# LCD_IO.net
KiCad netlist of a schematic drawn in Altium Designer
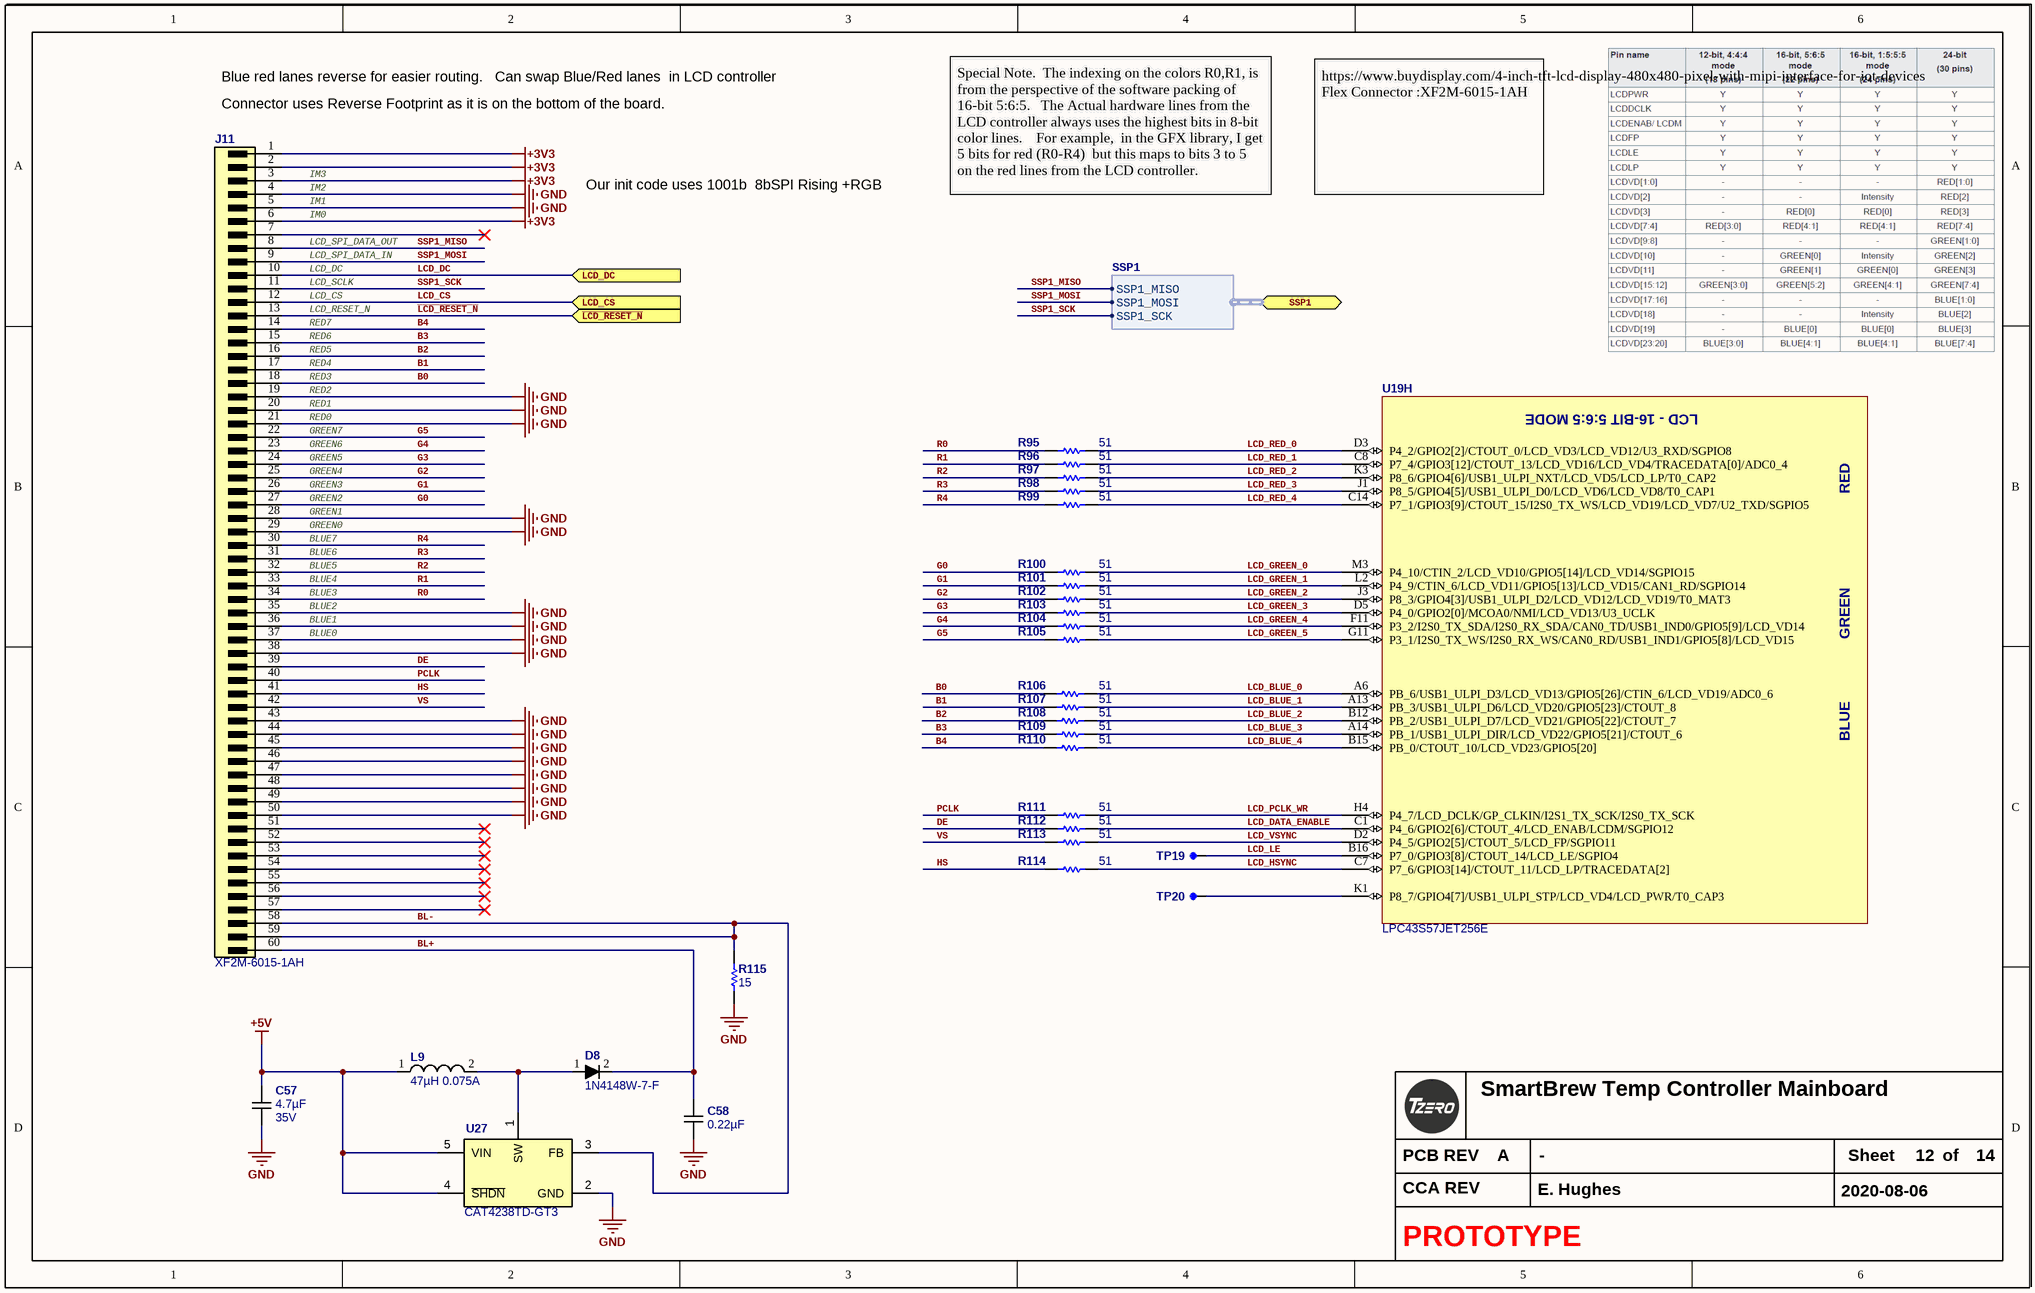
[diagram p0: LCD_IO.SchDoc]

(export (version "E")
  (design (tool "Eeschema 10.0.6"))
  (components
    (comp (ref "C57")
      (value "4.7µF")
      (footprint "C0805_1.50MM_HD")
      (description "CAP CER 4.7UF 35V X7R 0805")
      (fields
        (field (name "MANUFACTURER PART NUMBER") "CGA4J1X7R1V475K125AE")
        (field (name "MANUFACTURER") "TDK Corporation")
        (field (name "VOLTAGE - RATED") "35V")
      )
      (libsource (lib "Capacitors - TDK- AEC-Q200") (part "C_2P_NP"))
    )
    (comp (ref "C58")
      (value "0.22µF")
      (footprint "C0603_0.90MM_HD")
      (description "CAP CER 0.22UF 50V X7R 0603")
      (fields
        (field (name "MANUFACTURER PART NUMBER") "CGA3E3X7R1H224K080AB")
        (field (name "MANUFACTURER") "TDK Corporation")
      )
      (libsource (lib "Capacitors - TDK- AEC-Q200") (part "C_2P_NP"))
    )
    (comp (ref "D8")
      (value "1N4148W-7-F")
      (footprint "D_SOD-123_P")
      (description "DIODE SWITCH 100V 150MA SOD123")
      (fields (field (name "MANUFACTURER") "Diodes Inc"))
      (libsource (lib "Diodes") (part "DP_1A_2C"))
    )
    (comp (ref "J11")
      (value "XF2M-6015-1AH")
      (footprint "XF2M-6015-1AH - Reverse")
      (description "CONN FPC 60POS 0.50MM R/A")
      (fields (field (name "MANUFACTURER") "Omron"))
      (libsource (lib "eConnector_FPC") (part "XF2M-6015-1AH"))
    )
    (comp (ref "L9")
      (value "47µH 0.075A")
      (footprint "L0805_1.45MM_MD")
      (description "Inductor 47µH 0.075A")
      (fields (field (name "PART NUMBER") "LBR2012T470KV") (field (name "MANUFACTURER") "Taiyo Yuden"))
      (libsource (lib "Inductors") (part "L_2P"))
    )
    (comp (ref "R95")
      (value "51")
      (footprint "R0603_0.55MM_MD")
      (description "RES 51 OHM 1/10W 1% 0603 SMD")
      (fields
        (field (name "MANUFACTURER PART NUMBER") "ERJ-3EKF51R0V")
        (field (name "MANUFACTURER") "Panasonic Electronic Components")
      )
      (libsource (lib "Resistors - Panasonic - AEC-Q200") (part "R_2P"))
    )
    (comp (ref "R96")
      (value "51")
      (footprint "R0603_0.55MM_MD")
      (description "RES 51 OHM 1/10W 1% 0603 SMD")
      (fields
        (field (name "MANUFACTURER PART NUMBER") "ERJ-3EKF51R0V")
        (field (name "MANUFACTURER") "Panasonic Electronic Components")
      )
      (libsource (lib "Resistors - Panasonic - AEC-Q200") (part "R_2P"))
    )
    (comp (ref "R97")
      (value "51")
      (footprint "R0603_0.55MM_MD")
      (description "RES 51 OHM 1/10W 1% 0603 SMD")
      (fields
        (field (name "MANUFACTURER PART NUMBER") "ERJ-3EKF51R0V")
        (field (name "MANUFACTURER") "Panasonic Electronic Components")
      )
      (libsource (lib "Resistors - Panasonic - AEC-Q200") (part "R_2P"))
    )
    (comp (ref "R98")
      (value "51")
      (footprint "R0603_0.55MM_MD")
      (description "RES 51 OHM 1/10W 1% 0603 SMD")
      (fields
        (field (name "MANUFACTURER PART NUMBER") "ERJ-3EKF51R0V")
        (field (name "MANUFACTURER") "Panasonic Electronic Components")
      )
      (libsource (lib "Resistors - Panasonic - AEC-Q200") (part "R_2P"))
    )
    (comp (ref "R99")
      (value "51")
      (footprint "R0603_0.55MM_MD")
      (description "RES 51 OHM 1/10W 1% 0603 SMD")
      (fields
        (field (name "MANUFACTURER PART NUMBER") "ERJ-3EKF51R0V")
        (field (name "MANUFACTURER") "Panasonic Electronic Components")
      )
      (libsource (lib "Resistors - Panasonic - AEC-Q200") (part "R_2P"))
    )
    (comp (ref "R100")
      (value "51")
      (footprint "R0603_0.55MM_MD")
      (description "RES 51 OHM 1/10W 1% 0603 SMD")
      (fields
        (field (name "MANUFACTURER PART NUMBER") "ERJ-3EKF51R0V")
        (field (name "MANUFACTURER") "Panasonic Electronic Components")
      )
      (libsource (lib "Resistors - Panasonic - AEC-Q200") (part "R_2P"))
    )
    (comp (ref "R101")
      (value "51")
      (footprint "R0603_0.55MM_MD")
      (description "RES 51 OHM 1/10W 1% 0603 SMD")
      (fields
        (field (name "MANUFACTURER PART NUMBER") "ERJ-3EKF51R0V")
        (field (name "MANUFACTURER") "Panasonic Electronic Components")
      )
      (libsource (lib "Resistors - Panasonic - AEC-Q200") (part "R_2P"))
    )
    (comp (ref "R102")
      (value "51")
      (footprint "R0603_0.55MM_MD")
      (description "RES 51 OHM 1/10W 1% 0603 SMD")
      (fields
        (field (name "MANUFACTURER PART NUMBER") "ERJ-3EKF51R0V")
        (field (name "MANUFACTURER") "Panasonic Electronic Components")
      )
      (libsource (lib "Resistors - Panasonic - AEC-Q200") (part "R_2P"))
    )
    (comp (ref "R103")
      (value "51")
      (footprint "R0603_0.55MM_MD")
      (description "RES 51 OHM 1/10W 1% 0603 SMD")
      (fields
        (field (name "MANUFACTURER PART NUMBER") "ERJ-3EKF51R0V")
        (field (name "MANUFACTURER") "Panasonic Electronic Components")
      )
      (libsource (lib "Resistors - Panasonic - AEC-Q200") (part "R_2P"))
    )
    (comp (ref "R104")
      (value "51")
      (footprint "R0603_0.55MM_MD")
      (description "RES 51 OHM 1/10W 1% 0603 SMD")
      (fields
        (field (name "MANUFACTURER PART NUMBER") "ERJ-3EKF51R0V")
        (field (name "MANUFACTURER") "Panasonic Electronic Components")
      )
      (libsource (lib "Resistors - Panasonic - AEC-Q200") (part "R_2P"))
    )
    (comp (ref "R105")
      (value "51")
      (footprint "R0603_0.55MM_MD")
      (description "RES 51 OHM 1/10W 1% 0603 SMD")
      (fields
        (field (name "MANUFACTURER PART NUMBER") "ERJ-3EKF51R0V")
        (field (name "MANUFACTURER") "Panasonic Electronic Components")
      )
      (libsource (lib "Resistors - Panasonic - AEC-Q200") (part "R_2P"))
    )
    (comp (ref "R106")
      (value "51")
      (footprint "R0603_0.55MM_MD")
      (description "RES 51 OHM 1/10W 1% 0603 SMD")
      (fields
        (field (name "MANUFACTURER PART NUMBER") "ERJ-3EKF51R0V")
        (field (name "MANUFACTURER") "Panasonic Electronic Components")
      )
      (libsource (lib "Resistors - Panasonic - AEC-Q200") (part "R_2P"))
    )
    (comp (ref "R107")
      (value "51")
      (footprint "R0603_0.55MM_MD")
      (description "RES 51 OHM 1/10W 1% 0603 SMD")
      (fields
        (field (name "MANUFACTURER PART NUMBER") "ERJ-3EKF51R0V")
        (field (name "MANUFACTURER") "Panasonic Electronic Components")
      )
      (libsource (lib "Resistors - Panasonic - AEC-Q200") (part "R_2P"))
    )
    (comp (ref "R108")
      (value "51")
      (footprint "R0603_0.55MM_MD")
      (description "RES 51 OHM 1/10W 1% 0603 SMD")
      (fields
        (field (name "MANUFACTURER PART NUMBER") "ERJ-3EKF51R0V")
        (field (name "MANUFACTURER") "Panasonic Electronic Components")
      )
      (libsource (lib "Resistors - Panasonic - AEC-Q200") (part "R_2P"))
    )
    (comp (ref "R109")
      (value "51")
      (footprint "R0603_0.55MM_MD")
      (description "RES 51 OHM 1/10W 1% 0603 SMD")
      (fields
        (field (name "MANUFACTURER PART NUMBER") "ERJ-3EKF51R0V")
        (field (name "MANUFACTURER") "Panasonic Electronic Components")
      )
      (libsource (lib "Resistors - Panasonic - AEC-Q200") (part "R_2P"))
    )
    (comp (ref "R110")
      (value "51")
      (footprint "R0603_0.55MM_MD")
      (description "RES 51 OHM 1/10W 1% 0603 SMD")
      (fields
        (field (name "MANUFACTURER PART NUMBER") "ERJ-3EKF51R0V")
        (field (name "MANUFACTURER") "Panasonic Electronic Components")
      )
      (libsource (lib "Resistors - Panasonic - AEC-Q200") (part "R_2P"))
    )
    (comp (ref "R111")
      (value "51")
      (footprint "R0603_0.55MM_MD")
      (description "RES 51 OHM 1/10W 1% 0603 SMD")
      (fields
        (field (name "MANUFACTURER PART NUMBER") "ERJ-3EKF51R0V")
        (field (name "MANUFACTURER") "Panasonic Electronic Components")
      )
      (libsource (lib "Resistors - Panasonic - AEC-Q200") (part "R_2P"))
    )
    (comp (ref "R112")
      (value "51")
      (footprint "R0603_0.55MM_MD")
      (description "RES 51 OHM 1/10W 1% 0603 SMD")
      (fields
        (field (name "MANUFACTURER PART NUMBER") "ERJ-3EKF51R0V")
        (field (name "MANUFACTURER") "Panasonic Electronic Components")
      )
      (libsource (lib "Resistors - Panasonic - AEC-Q200") (part "R_2P"))
    )
    (comp (ref "R113")
      (value "51")
      (footprint "R0603_0.55MM_MD")
      (description "RES 51 OHM 1/10W 1% 0603 SMD")
      (fields
        (field (name "MANUFACTURER PART NUMBER") "ERJ-3EKF51R0V")
        (field (name "MANUFACTURER") "Panasonic Electronic Components")
      )
      (libsource (lib "Resistors - Panasonic - AEC-Q200") (part "R_2P"))
    )
    (comp (ref "R114")
      (value "51")
      (footprint "R0603_0.55MM_MD")
      (description "RES 51 OHM 1/10W 1% 0603 SMD")
      (fields
        (field (name "MANUFACTURER PART NUMBER") "ERJ-3EKF51R0V")
        (field (name "MANUFACTURER") "Panasonic Electronic Components")
      )
      (libsource (lib "Resistors - Panasonic - AEC-Q200") (part "R_2P"))
    )
    (comp (ref "R115")
      (value "15")
      (footprint "R0603_0.55MM_MD")
      (description "RES 15 OHM 1/10W 1% 0603 SMD")
      (fields
        (field (name "MANUFACTURER PART NUMBER") "ERJ-3EKF15R0V")
        (field (name "MANUFACTURER") "Panasonic Electronic Components")
      )
      (libsource (lib "Resistors - Panasonic - AEC-Q200") (part "R_2P"))
    )
    (comp (ref "TP19")
      (value "~")
      (footprint "Test Points-N:TP_SMT_25_MIL_ROUND")
      (libsource (lib "Test Points-N") (part "TP SMT 25MIL"))
    )
    (comp (ref "TP20")
      (value "~")
      (footprint "Test Points-N:TP_SMT_25_MIL_ROUND")
      (libsource (lib "Test Points-N") (part "TP SMT 25MIL"))
    )
    (comp (ref "U19")
      (value "LPC43S57JET256E")
      (footprint "Integrated Circuits BGA-N:LBGA256 16X16 1700X1700X155")
      (description "ARM Microcontrollers - MCU CortexM0/4 32bit 1MB Cortex-M4/M0")
      (fields (field (name "MANUFACTURER") "NXP Semiconductors"))
      (libsource (lib "eIC") (part "LPC43S57JET256E"))
    )
    (comp (ref "U27")
      (value "CAT4238TD-GT3")
      (footprint "SOT23-5")
      (description "IC LED DRIVER RGLTR DIM TSOT23-5")
      (fields (field (name "MANUFACTURER") "ON Semiconductor"))
      (libsource (lib "eIC_Regulator") (part "CAT4238TD-GT3"))
    )
  )
  (nets
    (net (code "2") (name "+3V3") (class "Default")
      (node (ref "J11") (pin "1") (pinfunction "1_1") (pintype "power_in"))
      (node (ref "J11") (pin "2") (pinfunction "2_2") (pintype "power_in"))
      (node (ref "J11") (pin "3") (pinfunction "3_3") (pintype "power_in"))
      (node (ref "J11") (pin "6") (pinfunction "6_6") (pintype "passive"))
    )
    (net (code "3") (name "+5V") (class "Default")
      (node (ref "C57") (pin "2") (pinfunction "1_2") (pintype "passive"))
      (node (ref "L9") (pin "1") (pinfunction "1_1") (pintype "passive"))
      (node (ref "U27") (pin "4") (pinfunction "~{SHDN}_4") (pintype "passive"))
      (node (ref "U27") (pin "5") (pinfunction "VIN_5") (pintype "passive"))
    )
    (net (code "4") (name "/B0") (class "Default")
      (node (ref "J11") (pin "18") (pinfunction "18_18") (pintype "passive"))
      (node (ref "R106") (pin "1") (pinfunction "1_1") (pintype "passive"))
    )
    (net (code "5") (name "/B1") (class "Default")
      (node (ref "J11") (pin "17") (pinfunction "17_17") (pintype "passive"))
      (node (ref "R107") (pin "1") (pinfunction "1_1") (pintype "passive"))
    )
    (net (code "6") (name "/B2") (class "Default")
      (node (ref "J11") (pin "16") (pinfunction "16_16") (pintype "passive"))
      (node (ref "R108") (pin "1") (pinfunction "1_1") (pintype "passive"))
    )
    (net (code "7") (name "/B3") (class "Default")
      (node (ref "J11") (pin "15") (pinfunction "15_15") (pintype "passive"))
      (node (ref "R109") (pin "1") (pinfunction "1_1") (pintype "passive"))
    )
    (net (code "8") (name "/B4") (class "Default")
      (node (ref "J11") (pin "14") (pinfunction "14_14") (pintype "passive"))
      (node (ref "R110") (pin "1") (pinfunction "1_1") (pintype "passive"))
    )
    (net (code "9") (name "/BL+") (class "Default")
      (node (ref "C58") (pin "2") (pinfunction "1_2") (pintype "passive"))
      (node (ref "D8") (pin "2") (pinfunction "K_2") (pintype "passive"))
      (node (ref "J11") (pin "60") (pinfunction "60_60") (pintype "passive"))
    )
    (net (code "10") (name "/BL-") (class "Default")
      (node (ref "J11") (pin "58") (pinfunction "58_58") (pintype "passive"))
      (node (ref "J11") (pin "59") (pinfunction "59_59") (pintype "passive"))
      (node (ref "R115") (pin "2") (pinfunction "2_2") (pintype "passive"))
      (node (ref "U27") (pin "3") (pinfunction "FB_3") (pintype "passive"))
    )
    (net (code "11") (name "/DE") (class "Default")
      (node (ref "J11") (pin "39") (pinfunction "39_39") (pintype "passive"))
      (node (ref "R112") (pin "1") (pinfunction "1_1") (pintype "passive"))
    )
    (net (code "12") (name "/G0") (class "Default")
      (node (ref "J11") (pin "27") (pinfunction "27_27") (pintype "passive"))
      (node (ref "R100") (pin "1") (pinfunction "1_1") (pintype "passive"))
    )
    (net (code "13") (name "/G1") (class "Default")
      (node (ref "J11") (pin "26") (pinfunction "26_26") (pintype "passive"))
      (node (ref "R101") (pin "1") (pinfunction "1_1") (pintype "passive"))
    )
    (net (code "14") (name "/G2") (class "Default")
      (node (ref "J11") (pin "25") (pinfunction "25_25") (pintype "passive"))
      (node (ref "R102") (pin "1") (pinfunction "1_1") (pintype "passive"))
    )
    (net (code "15") (name "/G3") (class "Default")
      (node (ref "J11") (pin "24") (pinfunction "24_24") (pintype "passive"))
      (node (ref "R103") (pin "1") (pinfunction "1_1") (pintype "passive"))
    )
    (net (code "16") (name "/G4") (class "Default")
      (node (ref "J11") (pin "23") (pinfunction "23_23") (pintype "passive"))
      (node (ref "R104") (pin "1") (pinfunction "1_1") (pintype "passive"))
    )
    (net (code "17") (name "/G5") (class "Default")
      (node (ref "J11") (pin "22") (pinfunction "22_22") (pintype "passive"))
      (node (ref "R105") (pin "1") (pinfunction "1_1") (pintype "passive"))
    )
    (net (code "18") (name "/HS") (class "Default")
      (node (ref "J11") (pin "41") (pinfunction "41_41") (pintype "passive"))
      (node (ref "R114") (pin "1") (pinfunction "1_1") (pintype "passive"))
    )
    (net (code "19") (name "/LCD_BLUE_0") (class "Default")
      (node (ref "R106") (pin "2") (pinfunction "2_2") (pintype "passive"))
      (node (ref "U19") (pin "A6") (pinfunction "PB_6/USB1_ULPI_D3/LCD_VD13/GPIO5[26]/CTIN_6/LCD_VD19/ADC0_6_A6") (pintype "bidirectional"))
    )
    (net (code "20") (name "/LCD_BLUE_1") (class "Default")
      (node (ref "R107") (pin "2") (pinfunction "2_2") (pintype "passive"))
      (node (ref "U19") (pin "A13") (pinfunction "PB_3/USB1_ULPI_D6/LCD_VD20/GPIO5[23]/CTOUT_8_A13") (pintype "bidirectional"))
    )
    (net (code "21") (name "/LCD_BLUE_2") (class "Default")
      (node (ref "R108") (pin "2") (pinfunction "2_2") (pintype "passive"))
      (node (ref "U19") (pin "B12") (pinfunction "PB_2/USB1_ULPI_D7/LCD_VD21/GPIO5[22]/CTOUT_7_B12") (pintype "bidirectional"))
    )
    (net (code "22") (name "/LCD_BLUE_3") (class "Default")
      (node (ref "R109") (pin "2") (pinfunction "2_2") (pintype "passive"))
      (node (ref "U19") (pin "A14") (pinfunction "PB_1/USB1_ULPI_DIR/LCD_VD22/GPIO5[21]/CTOUT_6_A14") (pintype "bidirectional"))
    )
    (net (code "23") (name "/LCD_BLUE_4") (class "Default")
      (node (ref "R110") (pin "2") (pinfunction "2_2") (pintype "passive"))
      (node (ref "U19") (pin "B15") (pinfunction "PB_0/CTOUT_10/LCD_VD23/GPIO5[20]_B15") (pintype "bidirectional"))
    )
    (net (code "24") (name "/LCD_CS") (class "Default")
      (node (ref "J11") (pin "12") (pinfunction "12_12") (pintype "passive"))
    )
    (net (code "25") (name "/LCD_DATA_ENABLE") (class "Default")
      (node (ref "R112") (pin "2") (pinfunction "2_2") (pintype "passive"))
      (node (ref "U19") (pin "C1") (pinfunction "P4_6/GPIO2[6]/CTOUT_4/LCD_ENAB/LCDM/SGPIO12_C1") (pintype "bidirectional"))
    )
    (net (code "26") (name "/LCD_DC") (class "Default")
      (node (ref "J11") (pin "10") (pinfunction "10_10") (pintype "passive"))
    )
    (net (code "27") (name "/LCD_GREEN_0") (class "Default")
      (node (ref "R100") (pin "2") (pinfunction "2_2") (pintype "passive"))
      (node (ref "U19") (pin "M3") (pinfunction "P4_10/CTIN_2/LCD_VD10/GPIO5[14]/LCD_VD14/SGPIO15_M3") (pintype "bidirectional"))
    )
    (net (code "28") (name "/LCD_GREEN_1") (class "Default")
      (node (ref "R101") (pin "2") (pinfunction "2_2") (pintype "passive"))
      (node (ref "U19") (pin "L2") (pinfunction "P4_9/CTIN_6/LCD_VD11/GPIO5[13]/LCD_VD15/CAN1_RD/SGPIO14_L2") (pintype "bidirectional"))
    )
    (net (code "29") (name "/LCD_GREEN_2") (class "Default")
      (node (ref "R102") (pin "2") (pinfunction "2_2") (pintype "passive"))
      (node (ref "U19") (pin "J3") (pinfunction "P8_3/GPIO4[3]/USB1_ULPI_D2/LCD_VD12/LCD_VD19/T0_MAT3_J3") (pintype "bidirectional"))
    )
    (net (code "30") (name "/LCD_GREEN_3") (class "Default")
      (node (ref "R103") (pin "2") (pinfunction "2_2") (pintype "passive"))
      (node (ref "U19") (pin "D5") (pinfunction "P4_0/GPIO2[0]/MCOA0/NMI/LCD_VD13/U3_UCLK_D5") (pintype "bidirectional"))
    )
    (net (code "31") (name "/LCD_GREEN_4") (class "Default")
      (node (ref "R104") (pin "2") (pinfunction "2_2") (pintype "passive"))
      (node (ref "U19") (pin "F11") (pinfunction "P3_2/I2S0_TX_SDA/I2S0_RX_SDA/CAN0_TD/USB1_IND0/GPIO5[9]/LCD_VD14_F11") (pintype "bidirectional"))
    )
    (net (code "32") (name "/LCD_GREEN_5") (class "Default")
      (node (ref "R105") (pin "2") (pinfunction "2_2") (pintype "passive"))
      (node (ref "U19") (pin "G11") (pinfunction "P3_1/I2S0_TX_WS/I2S0_RX_WS/CAN0_RD/USB1_IND1/GPIO5[8]/LCD_VD15_G11") (pintype "bidirectional"))
    )
    (net (code "33") (name "/LCD_HSYNC") (class "Default")
      (node (ref "R114") (pin "2") (pinfunction "2_2") (pintype "passive"))
      (node (ref "U19") (pin "C7") (pinfunction "P7_6/GPIO3[14]/CTOUT_11/LCD_LP/TRACEDATA[2]_C7") (pintype "bidirectional"))
    )
    (net (code "34") (name "/LCD_LE") (class "Default")
      (node (ref "TP19") (pin "1") (pinfunction "1_1") (pintype "passive"))
      (node (ref "U19") (pin "B16") (pinfunction "P7_0/GPIO3[8]/CTOUT_14/LCD_LE/SGPIO4_B16") (pintype "bidirectional"))
    )
    (net (code "35") (name "/LCD_PCLK_WR") (class "Default")
      (node (ref "R111") (pin "2") (pinfunction "2_2") (pintype "passive"))
      (node (ref "U19") (pin "H4") (pinfunction "P4_7/LCD_DCLK/GP_CLKIN/I2S1_TX_SCK/I2S0_TX_SCK_H4") (pintype "bidirectional"))
    )
    (net (code "36") (name "/LCD_RED_0") (class "Default")
      (node (ref "R95") (pin "2") (pinfunction "2_2") (pintype "passive"))
      (node (ref "U19") (pin "D3") (pinfunction "P4_2/GPIO2[2]/CTOUT_0/LCD_VD3/LCD_VD12/U3_RXD/SGPIO8_D3") (pintype "bidirectional"))
    )
    (net (code "37") (name "/LCD_RED_1") (class "Default")
      (node (ref "R96") (pin "2") (pinfunction "2_2") (pintype "passive"))
      (node (ref "U19") (pin "C8") (pinfunction "P7_4/GPIO3[12]/CTOUT_13/LCD_VD16/LCD_VD4/TRACEDATA[0]/ADC0_4_C8") (pintype "bidirectional"))
    )
    (net (code "38") (name "/LCD_RED_2") (class "Default")
      (node (ref "R97") (pin "2") (pinfunction "2_2") (pintype "passive"))
      (node (ref "U19") (pin "K3") (pinfunction "P8_6/GPIO4[6]/USB1_ULPI_NXT/LCD_VD5/LCD_LP/T0_CAP2_K3") (pintype "bidirectional"))
    )
    (net (code "39") (name "/LCD_RED_3") (class "Default")
      (node (ref "R98") (pin "2") (pinfunction "2_2") (pintype "passive"))
      (node (ref "U19") (pin "J1") (pinfunction "P8_5/GPIO4[5]/USB1_ULPI_D0/LCD_VD6/LCD_VD8/T0_CAP1_J1") (pintype "bidirectional"))
    )
    (net (code "40") (name "/LCD_RED_4") (class "Default")
      (node (ref "R99") (pin "2") (pinfunction "2_2") (pintype "passive"))
      (node (ref "U19") (pin "C14") (pinfunction "P7_1/GPIO3[9]/CTOUT_15/I2S0_TX_WS/LCD_VD19/LCD_VD7/U2_TXD/SGPIO5_C14") (pintype "bidirectional"))
    )
    (net (code "41") (name "/LCD_RESET_N") (class "Default")
      (node (ref "J11") (pin "13") (pinfunction "13_13") (pintype "passive"))
    )
    (net (code "42") (name "/LCD_VSYNC") (class "Default")
      (node (ref "R113") (pin "2") (pinfunction "2_2") (pintype "passive"))
      (node (ref "U19") (pin "D2") (pinfunction "P4_5/GPIO2[5]/CTOUT_5/LCD_FP/SGPIO11_D2") (pintype "bidirectional"))
    )
    (net (code "43") (name "/PCLK") (class "Default")
      (node (ref "J11") (pin "40") (pinfunction "40_40") (pintype "passive"))
      (node (ref "R111") (pin "1") (pinfunction "1_1") (pintype "passive"))
    )
    (net (code "44") (name "/R0") (class "Default")
      (node (ref "J11") (pin "34") (pinfunction "34_34") (pintype "passive"))
      (node (ref "R95") (pin "1") (pinfunction "1_1") (pintype "passive"))
    )
    (net (code "45") (name "/R1") (class "Default")
      (node (ref "J11") (pin "33") (pinfunction "33_33") (pintype "passive"))
      (node (ref "R96") (pin "1") (pinfunction "1_1") (pintype "passive"))
    )
    (net (code "46") (name "/R2") (class "Default")
      (node (ref "J11") (pin "32") (pinfunction "32_32") (pintype "passive"))
      (node (ref "R97") (pin "1") (pinfunction "1_1") (pintype "passive"))
    )
    (net (code "47") (name "/R3") (class "Default")
      (node (ref "J11") (pin "31") (pinfunction "31_31") (pintype "passive"))
      (node (ref "R98") (pin "1") (pinfunction "1_1") (pintype "passive"))
    )
    (net (code "48") (name "/R4") (class "Default")
      (node (ref "J11") (pin "30") (pinfunction "30_30") (pintype "passive"))
      (node (ref "R99") (pin "1") (pinfunction "1_1") (pintype "passive"))
    )
    (net (code "49") (name "/SSP1_MISO") (class "Default")
      (node (ref "J11") (pin "8") (pinfunction "8_8") (pintype "passive"))
    )
    (net (code "50") (name "/SSP1_MOSI") (class "Default")
      (node (ref "J11") (pin "9") (pinfunction "9_9") (pintype "passive"))
    )
    (net (code "51") (name "/SSP1_SCK") (class "Default")
      (node (ref "J11") (pin "11") (pinfunction "11_11") (pintype "passive"))
    )
    (net (code "52") (name "/VS") (class "Default")
      (node (ref "J11") (pin "42") (pinfunction "42_42") (pintype "passive"))
      (node (ref "R113") (pin "1") (pinfunction "1_1") (pintype "passive"))
    )
    (net (code "54") (name "GND") (class "Default")
      (node (ref "C57") (pin "1") (pinfunction "1_1") (pintype "passive"))
      (node (ref "C58") (pin "1") (pinfunction "1_1") (pintype "passive"))
      (node (ref "J11") (pin "19") (pinfunction "19_19") (pintype "passive"))
      (node (ref "J11") (pin "20") (pinfunction "20_20") (pintype "passive"))
      (node (ref "J11") (pin "21") (pinfunction "21_21") (pintype "passive"))
      (node (ref "J11") (pin "28") (pinfunction "28_28") (pintype "passive"))
      (node (ref "J11") (pin "29") (pinfunction "29_29") (pintype "passive"))
      (node (ref "J11") (pin "35") (pinfunction "35_35") (pintype "passive"))
      (node (ref "J11") (pin "36") (pinfunction "36_36") (pintype "passive"))
      (node (ref "J11") (pin "37") (pinfunction "37_37") (pintype "passive"))
      (node (ref "J11") (pin "38") (pinfunction "XR_38") (pintype "passive"))
      (node (ref "J11") (pin "4") (pinfunction "4_4") (pintype "power_in"))
      (node (ref "J11") (pin "43") (pinfunction "43_43") (pintype "passive"))
      (node (ref "J11") (pin "44") (pinfunction "44_44") (pintype "passive"))
      (node (ref "J11") (pin "45") (pinfunction "45_45") (pintype "passive"))
      (node (ref "J11") (pin "46") (pinfunction "46_46") (pintype "passive"))
      (node (ref "J11") (pin "47") (pinfunction "47_47") (pintype "passive"))
      (node (ref "J11") (pin "48") (pinfunction "48_48") (pintype "passive"))
      (node (ref "J11") (pin "49") (pinfunction "19_49") (pintype "passive"))
      (node (ref "J11") (pin "5") (pinfunction "5_5") (pintype "passive"))
      (node (ref "J11") (pin "50") (pinfunction "50_50") (pintype "passive"))
      (node (ref "R115") (pin "1") (pinfunction "1_1") (pintype "passive"))
      (node (ref "U27") (pin "2") (pinfunction "GND_2") (pintype "passive"))
    )
    (net (code "55") (name "Net-(D8-A)") (class "Default")
      (node (ref "D8") (pin "1") (pinfunction "A_1") (pintype "passive"))
      (node (ref "L9") (pin "2") (pinfunction "2_2") (pintype "passive"))
      (node (ref "U27") (pin "1") (pinfunction "SW_1") (pintype "passive"))
    )
    (net (code "56") (name "Net-(U19H-P8_7{slash}GPIO4[7]{slash}USB1_ULPI_STP{slash}LCD_VD4{slash}LCD_PWR{slash}T0_CAP3)") (class "Default")
      (node (ref "TP20") (pin "1") (pinfunction "1_1") (pintype "passive"))
      (node (ref "U19") (pin "K1") (pinfunction "P8_7/GPIO4[7]/USB1_ULPI_STP/LCD_VD4/LCD_PWR/T0_CAP3_K1") (pintype "bidirectional"))
    )
    (net (code "57") (name "unconnected-(J11-Pad7)") (class "Default")
      (node (ref "J11") (pin "7") (pinfunction "7_7") (pintype "passive+no_connect"))
    )
    (net (code "58") (name "unconnected-(J11-Pad51)") (class "Default")
      (node (ref "J11") (pin "51") (pinfunction "51_51") (pintype "passive+no_connect"))
    )
    (net (code "59") (name "unconnected-(J11-Pad52)") (class "Default")
      (node (ref "J11") (pin "52") (pinfunction "52_52") (pintype "passive+no_connect"))
    )
    (net (code "60") (name "unconnected-(J11-Pad53)") (class "Default")
      (node (ref "J11") (pin "53") (pinfunction "53_53") (pintype "passive+no_connect"))
    )
    (net (code "61") (name "unconnected-(J11-Pad54)") (class "Default")
      (node (ref "J11") (pin "54") (pinfunction "54_54") (pintype "passive+no_connect"))
    )
    (net (code "62") (name "unconnected-(J11-Pad55)") (class "Default")
      (node (ref "J11") (pin "55") (pinfunction "55_55") (pintype "passive+no_connect"))
    )
    (net (code "63") (name "unconnected-(J11-Pad56)") (class "Default")
      (node (ref "J11") (pin "56") (pinfunction "56_56") (pintype "passive+no_connect"))
    )
    (net (code "64") (name "unconnected-(J11-Pad57)") (class "Default")
      (node (ref "J11") (pin "57") (pinfunction "57_57") (pintype "passive+no_connect"))
    )
  )
)
